# SMPS_5V_D.net
KiCad netlist of a schematic drawn in Altium Designer
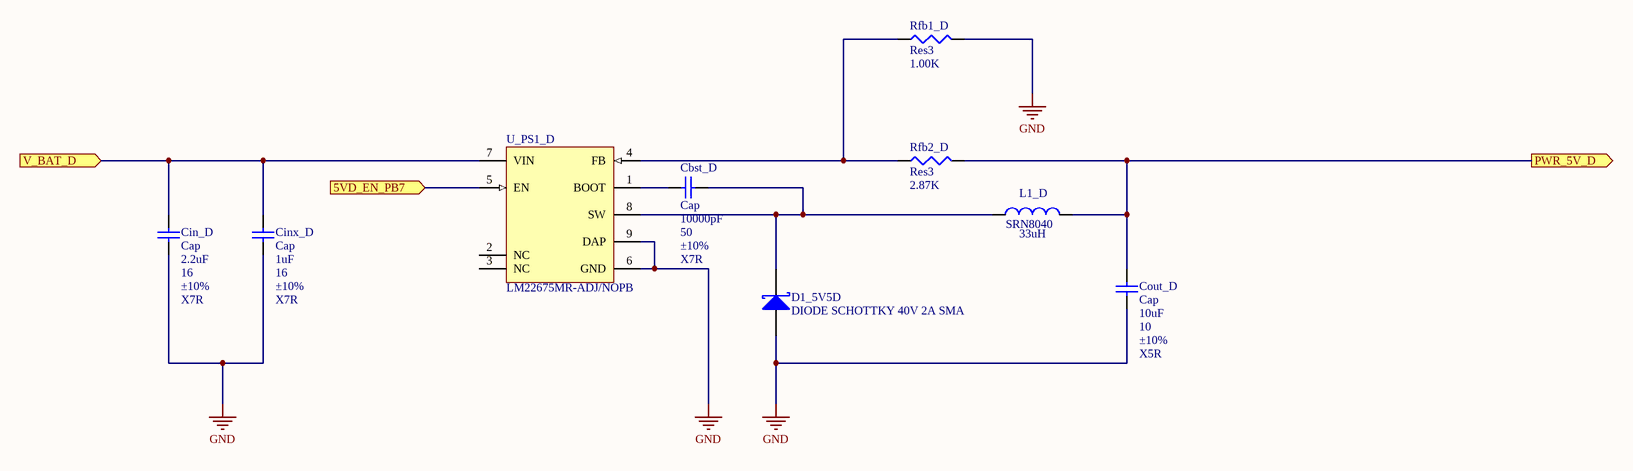
[diagram p0: SMPS_5V_D.SchDoc]

(export (version "E")
  (design (tool "Eeschema 10.0.6"))
  (components
    (comp (ref "Cbst_D")
      (value "Cap")
      (footprint "CAPC2012X09M")
      (description "CAP CER 10000pF 50v X7R 0805")
      (fields
        (field (name "ALTIUM_VALUE") "10000pF")
        (field (name "WV") "50")
        (field (name "TOLERANCE") "±10%")
        (field (name "TYPE") "X7R")
        (field (name "MPN") "C0805C103K5RACTU")
      )
      (libsource (lib "esd_library") (part "CAP-X7R-10000pF-50V-±10%"))
    )
    (comp (ref "Cinx_D")
      (value "Cap")
      (footprint "CAPC2012X09M")
      (description "CAP CER 1uF 16v X7R 0805")
      (fields
        (field (name "ALTIUM_VALUE") "1uF")
        (field (name "WV") "16")
        (field (name "TOLERANCE") "±10%")
        (field (name "TYPE") "X7R")
        (field (name "MPN") "C0805C105K4RACTU")
      )
      (libsource (lib "esd_library") (part "CAP-X7R-1uF-16V-±10%"))
    )
    (comp (ref "Cin_D")
      (value "Cap")
      (footprint "CAPC2012X09M")
      (description "CAP CER 2.2uF 16v X7R 0805")
      (fields
        (field (name "ALTIUM_VALUE") "2.2uF")
        (field (name "WV") "16")
        (field (name "TOLERANCE") "±10%")
        (field (name "TYPE") "X7R")
        (field (name "MPN") "C0805C225K4RACTU")
      )
      (libsource (lib "esd_library") (part "CAP-X7R-2.2uF-16V-±10%"))
    )
    (comp (ref "Cout_D")
      (value "Cap")
      (footprint "CAPC2012X09M")
      (description "CAP CER 10uF 10v X5R 0805")
      (fields
        (field (name "ALTIUM_VALUE") "10uF")
        (field (name "WV") "10")
        (field (name "TOLERANCE") "±10%")
        (field (name "TYPE") "X5R")
        (field (name "MPN") "C0805C106K8PACTU")
      )
      (libsource (lib "esd_library") (part "CAP-X5R-10uF-10V-±10%"))
    )
    (comp (ref "D1_5V5D")
      (value "DIODE SCHOTTKY 40V 2A SMA")
      (footprint "DIOM4326X23M")
      (description "Schottky Rectifier")
      (fields (field (name "MPN") "B240A-13-F"))
      (libsource (lib "esd_library") (part "DIODE SCHOTTKY 40V 2A SMA"))
    )
    (comp (ref "L1_D")
      (value "SRN8040")
      (footprint "INDP8080X40M")
      (description "FIXED IND 33UH 1.7A 145 MOHM SMD")
      (fields (field (name "MPN") "SRN8040-220M") (field (name "VAL") "33uH"))
      (libsource (lib "esd_library") (part "SRN8040"))
    )
    (comp (ref "Rfb1_D")
      (value "Res3")
      (footprint "RESC2112X05M")
      (description "RES SMD 1.00K OHM 1% 1/8W 0805")
      (fields (field (name "MPN") "CRCW08051K00FKEA") (field (name "ALTIUM_VALUE") "1.00K"))
      (libsource (lib "esd_library") (part "Resistor_1.00K"))
    )
    (comp (ref "Rfb2_D")
      (value "Res3")
      (footprint "RESC2112X05M")
      (description "RES SMD 2.87K OHM 1% 1/8W 0805")
      (fields (field (name "ALTIUM_VALUE") "2.87K") (field (name "MPN") "CRCW08052K87FKEA"))
      (libsource (lib "esd_library") (part "Resistor_2.87K"))
    )
    (comp (ref "U_PS1_D")
      (value "LM22675MR-ADJ/NOPB")
      (footprint "MRA08B_L")
      (description "1A SIMPLE SWITCHER®, Step-Down Voltage Regulator with Precision Enable, 8-pin PSOP, Pb-Free")
      (fields
        (field (name "MANUFACTURER") "National Semiconductor")
        (field (name "MPN") "LM22675MRE-ADJ/NOPB")
      )
      (libsource (lib "esd_library") (part "LM22675MR-ADJ/NOPB"))
    )
  )
  (nets
    (net (code "1") (name "/5VD_EN_PB7") (class "Default")
      (node (ref "U_PS1_D") (pin "5") (pinfunction "EN_5") (pintype "input"))
    )
    (net (code "2") (name "/PWR_5V_D") (class "Default")
      (node (ref "Cout_D") (pin "2") (pinfunction "2_2") (pintype "passive"))
      (node (ref "L1_D") (pin "2") (pinfunction "2_2") (pintype "passive"))
      (node (ref "Rfb2_D") (pin "2") (pinfunction "2_2") (pintype "passive"))
    )
    (net (code "3") (name "/V_BAT_D") (class "Default")
      (node (ref "Cin_D") (pin "2") (pinfunction "2_2") (pintype "passive"))
      (node (ref "Cinx_D") (pin "2") (pinfunction "2_2") (pintype "passive"))
      (node (ref "U_PS1_D") (pin "7") (pinfunction "VIN_7") (pintype "power_in"))
    )
    (net (code "4") (name "GND") (class "Default")
      (node (ref "Cin_D") (pin "1") (pinfunction "1_1") (pintype "passive"))
      (node (ref "Cinx_D") (pin "1") (pinfunction "1_1") (pintype "passive"))
      (node (ref "Cout_D") (pin "1") (pinfunction "1_1") (pintype "passive"))
      (node (ref "D1_5V5D") (pin "2") (pinfunction "A_2") (pintype "passive"))
      (node (ref "Rfb1_D") (pin "2") (pinfunction "2_2") (pintype "passive"))
      (node (ref "U_PS1_D") (pin "6") (pinfunction "GND_6") (pintype "power_in"))
      (node (ref "U_PS1_D") (pin "9") (pinfunction "DAP_9") (pintype "power_in"))
    )
    (net (code "5") (name "Net-(D1_5V5D-K)") (class "Default")
      (node (ref "Cbst_D") (pin "2") (pinfunction "2_2") (pintype "passive"))
      (node (ref "D1_5V5D") (pin "1") (pinfunction "K_1") (pintype "passive"))
      (node (ref "L1_D") (pin "1") (pinfunction "1_1") (pintype "passive"))
      (node (ref "U_PS1_D") (pin "8") (pinfunction "SW_8") (pintype "power_in"))
    )
    (net (code "6") (name "Net-(U_PS1_D-BOOT)") (class "Default")
      (node (ref "Cbst_D") (pin "1") (pinfunction "1_1") (pintype "passive"))
      (node (ref "U_PS1_D") (pin "1") (pinfunction "BOOT_1") (pintype "passive"))
    )
    (net (code "7") (name "Net-(U_PS1_D-FB)") (class "Default")
      (node (ref "Rfb1_D") (pin "1") (pinfunction "1_1") (pintype "passive"))
      (node (ref "Rfb2_D") (pin "1") (pinfunction "1_1") (pintype "passive"))
      (node (ref "U_PS1_D") (pin "4") (pinfunction "FB_4") (pintype "input"))
    )
    (net (code "8") (name "unconnected-(U_PS1_D-NC-Pad2)") (class "Default")
      (node (ref "U_PS1_D") (pin "2") (pinfunction "NC_2") (pintype "passive"))
    )
    (net (code "9") (name "unconnected-(U_PS1_D-NC-Pad3)") (class "Default")
      (node (ref "U_PS1_D") (pin "3") (pinfunction "NC_3") (pintype "passive"))
    )
  )
)
